# PCB.net
KiCad netlist of a schematic drawn in Altium Designer
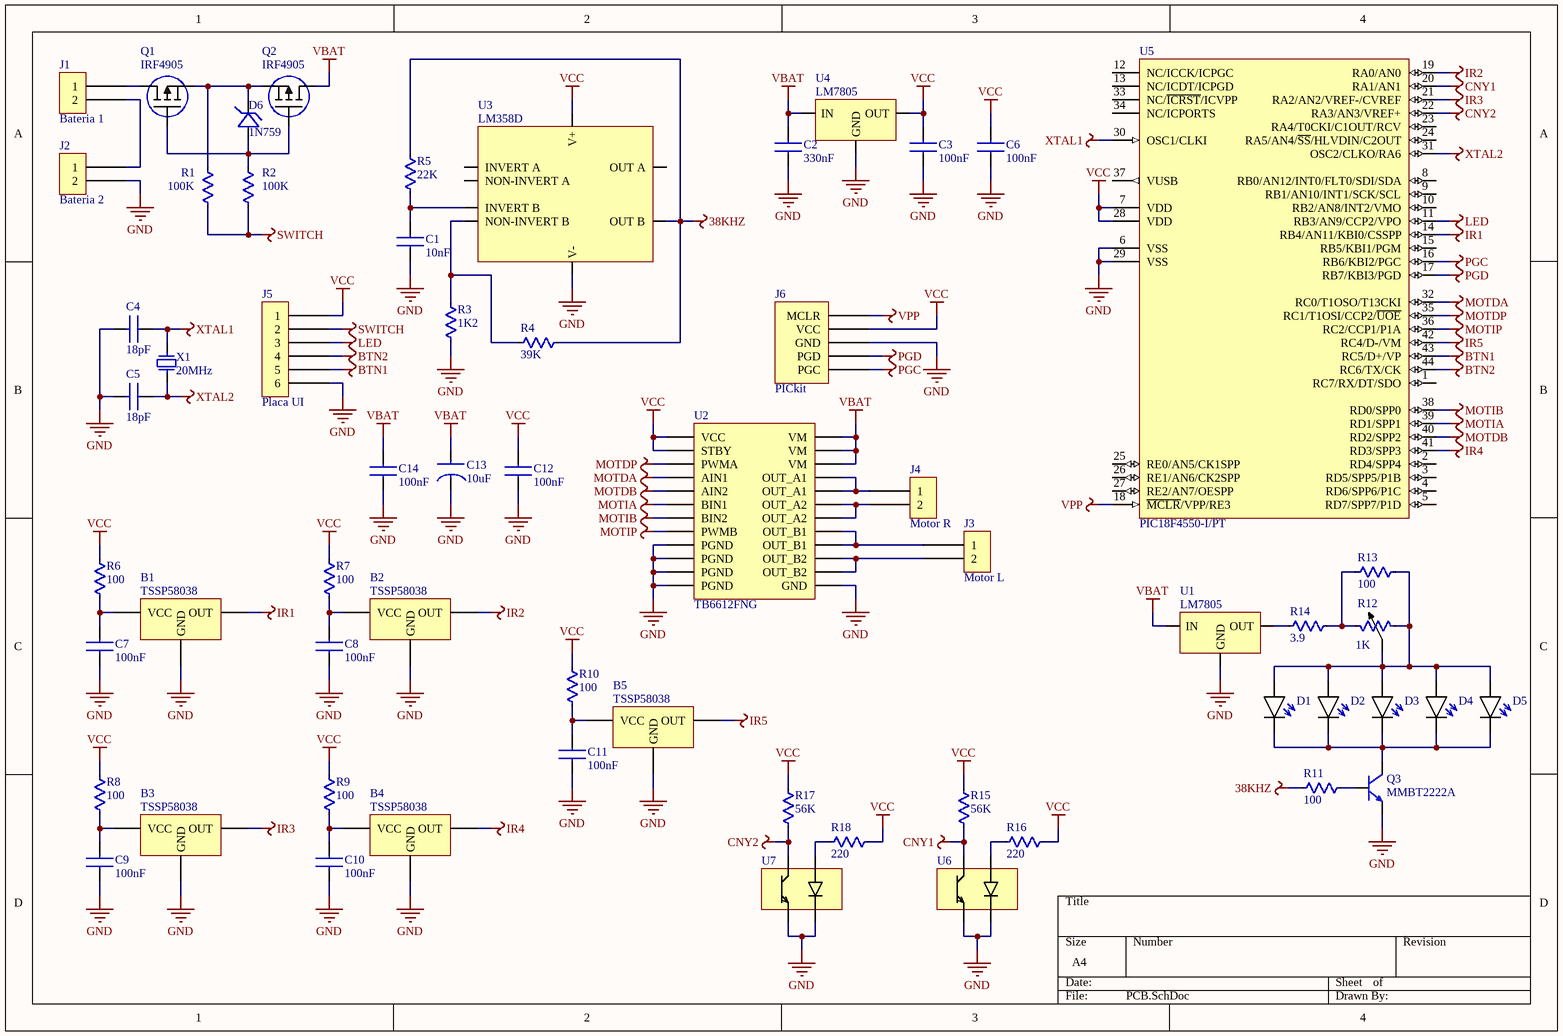
[diagram p0: PCB.SchDoc]

(export (version "E")
  (design (tool "Eeschema 10.0.6"))
  (components
    (comp (ref "B1")
      (value "TSSP58038")
      (footprint "TSSP58038")
      (libsource (lib "AltiumLibrary") (part "TSSP58038"))
    )
    (comp (ref "B2")
      (value "TSSP58038")
      (footprint "TSSP58038")
      (libsource (lib "AltiumLibrary") (part "TSSP58038"))
    )
    (comp (ref "B3")
      (value "TSSP58038")
      (footprint "TSSP58038")
      (libsource (lib "AltiumLibrary") (part "TSSP58038"))
    )
    (comp (ref "B4")
      (value "TSSP58038")
      (footprint "TSSP58038")
      (libsource (lib "AltiumLibrary") (part "TSSP58038"))
    )
    (comp (ref "B5")
      (value "TSSP58038")
      (footprint "TSSP58038")
      (libsource (lib "AltiumLibrary") (part "TSSP58038"))
    )
    (comp (ref "C1")
      (value "10nF")
      (footprint "C1206")
      (fields (field (name "Comment") "CAP-CER"))
      (libsource (lib "AltiumLibrary") (part "CAP-CER"))
    )
    (comp (ref "C2")
      (value "330nF")
      (footprint "C1206")
      (fields (field (name "Comment") "CAP-CER"))
      (libsource (lib "AltiumLibrary") (part "CAP-CER"))
    )
    (comp (ref "C3")
      (value "100nF")
      (footprint "C1206")
      (fields (field (name "Comment") "CAP-CER"))
      (libsource (lib "AltiumLibrary") (part "CAP-CER"))
    )
    (comp (ref "C4")
      (value "18pF")
      (footprint "C1206")
      (fields (field (name "Comment") "CAP-CER"))
      (libsource (lib "AltiumLibrary") (part "CAP-CER"))
    )
    (comp (ref "C5")
      (value "18pF")
      (footprint "C1206")
      (fields (field (name "Comment") "CAP-CER"))
      (libsource (lib "AltiumLibrary") (part "CAP-CER"))
    )
    (comp (ref "C6")
      (value "100nF")
      (footprint "C1206")
      (fields (field (name "Comment") "CAP-CER"))
      (libsource (lib "AltiumLibrary") (part "CAP-CER"))
    )
    (comp (ref "C7")
      (value "100nF")
      (footprint "C1206")
      (fields (field (name "Comment") "CAP-CER"))
      (libsource (lib "AltiumLibrary") (part "CAP-CER"))
    )
    (comp (ref "C8")
      (value "100nF")
      (footprint "C1206")
      (fields (field (name "Comment") "CAP-CER"))
      (libsource (lib "AltiumLibrary") (part "CAP-CER"))
    )
    (comp (ref "C9")
      (value "100nF")
      (footprint "C1206")
      (fields (field (name "Comment") "CAP-CER"))
      (libsource (lib "AltiumLibrary") (part "CAP-CER"))
    )
    (comp (ref "C10")
      (value "100nF")
      (footprint "C1206")
      (fields (field (name "Comment") "CAP-CER"))
      (libsource (lib "AltiumLibrary") (part "CAP-CER"))
    )
    (comp (ref "C11")
      (value "100nF")
      (footprint "C1206")
      (fields (field (name "Comment") "CAP-CER"))
      (libsource (lib "AltiumLibrary") (part "CAP-CER"))
    )
    (comp (ref "C12")
      (value "100nF")
      (footprint "C1206")
      (fields (field (name "Comment") "CAP-CER"))
      (libsource (lib "AltiumLibrary") (part "CAP-CER"))
    )
    (comp (ref "C13")
      (value "10uF")
      (footprint "CAP-ELEC-5x11x2mm")
      (fields (field (name "Comment") "CAP-ELEC"))
      (libsource (lib "AltiumLibrary") (part "CAP-ELEC"))
    )
    (comp (ref "C14")
      (value "100nF")
      (footprint "C1206")
      (fields (field (name "Comment") "CAP-CER"))
      (libsource (lib "AltiumLibrary") (part "CAP-CER"))
    )
    (comp (ref "D1") (value "LED") (footprint "LED-5MM-CLEAR") (libsource (lib "AltiumLibrary") (part "LED")))
    (comp (ref "D2") (value "LED") (footprint "LED-5MM-CLEAR") (libsource (lib "AltiumLibrary") (part "LED")))
    (comp (ref "D3") (value "LED") (footprint "LED-5MM-CLEAR") (libsource (lib "AltiumLibrary") (part "LED")))
    (comp (ref "D4") (value "LED") (footprint "LED-5MM-CLEAR") (libsource (lib "AltiumLibrary") (part "LED")))
    (comp (ref "D5") (value "LED") (footprint "LED-5MM-CLEAR") (libsource (lib "AltiumLibrary") (part "LED")))
    (comp (ref "D6") (value "1N759") (footprint "SOD-80") (libsource (lib "AltiumLibrary") (part "ZENER")))
    (comp (ref "J1") (value "Bateria 1") (footprint "HEADER 1x2") (libsource (lib "") (part "Header 1x2_1")))
    (comp (ref "J2") (value "Bateria 2") (footprint "HEADER 1x2") (libsource (lib "") (part "Header 1x2_1")))
    (comp (ref "J3")
      (value "Motor L")
      (footprint "HEADER 1x2")
      (libsource (lib "AltiumLibrary") (part "Header 1x2"))
    )
    (comp (ref "J4")
      (value "Motor R")
      (footprint "HEADER 1x2")
      (libsource (lib "AltiumLibrary") (part "Header 1x2"))
    )
    (comp (ref "J5")
      (value "Placa UI")
      (footprint "Header 1x6")
      (libsource (lib "AltiumLibrary") (part "Header 1x6"))
    )
    (comp (ref "J6")
      (value "PICkit")
      (footprint "Header 1x5")
      (libsource (lib "AltiumLibrary") (part "PICkit"))
    )
    (comp (ref "Q1")
      (value "IRF4905")
      (footprint "TO-220")
      (libsource (lib "AltiumLibrary") (part "P-MOSFET"))
    )
    (comp (ref "Q2")
      (value "IRF4905")
      (footprint "TO-220")
      (libsource (lib "AltiumLibrary") (part "P-MOSFET"))
    )
    (comp (ref "Q3") (value "MMBT2222A") (footprint "SOT-23") (libsource (lib "AltiumLibrary") (part "NPN")))
    (comp (ref "R1")
      (value "100K")
      (footprint "R1206")
      (fields (field (name "Comment") "RES"))
      (libsource (lib "") (part "RES_1"))
    )
    (comp (ref "R2")
      (value "100K")
      (footprint "R1206")
      (fields (field (name "Comment") "RES"))
      (libsource (lib "") (part "RES_2"))
    )
    (comp (ref "R3")
      (value "1K2")
      (footprint "R1206")
      (fields (field (name "Comment") "RES"))
      (libsource (lib "") (part "RES_2"))
    )
    (comp (ref "R4")
      (value "39K")
      (footprint "R1206")
      (fields (field (name "Comment") "RES"))
      (libsource (lib "AltiumLibrary") (part "RES"))
    )
    (comp (ref "R5")
      (value "22K")
      (footprint "R1206")
      (fields (field (name "Comment") "RES"))
      (libsource (lib "") (part "RES_2"))
    )
    (comp (ref "R6")
      (value "100")
      (footprint "R1206")
      (fields (field (name "Comment") "RES"))
      (libsource (lib "") (part "RES_2"))
    )
    (comp (ref "R7")
      (value "100")
      (footprint "R1206")
      (fields (field (name "Comment") "RES"))
      (libsource (lib "") (part "RES_2"))
    )
    (comp (ref "R8")
      (value "100")
      (footprint "R1206")
      (fields (field (name "Comment") "RES"))
      (libsource (lib "") (part "RES_2"))
    )
    (comp (ref "R9")
      (value "100")
      (footprint "R1206")
      (fields (field (name "Comment") "RES"))
      (libsource (lib "") (part "RES_2"))
    )
    (comp (ref "R10")
      (value "100")
      (footprint "R1206")
      (fields (field (name "Comment") "RES"))
      (libsource (lib "") (part "RES_2"))
    )
    (comp (ref "R11")
      (value "100")
      (footprint "R1206")
      (fields (field (name "Comment") "RES"))
      (libsource (lib "AltiumLibrary") (part "RES"))
    )
    (comp (ref "R12")
      (value "1K")
      (footprint "TRIMPOT")
      (fields (field (name "Comment") "POT"))
      (libsource (lib "AltiumLibrary") (part "POT"))
    )
    (comp (ref "R13")
      (value "100")
      (footprint "R1206")
      (fields (field (name "Comment") "RES"))
      (libsource (lib "AltiumLibrary") (part "RES"))
    )
    (comp (ref "R14")
      (value "3.9")
      (footprint "R1206")
      (fields (field (name "Comment") "RES"))
      (libsource (lib "AltiumLibrary") (part "RES"))
    )
    (comp (ref "R15")
      (value "56K")
      (footprint "R1206")
      (fields (field (name "Comment") "RES"))
      (libsource (lib "") (part "RES_2"))
    )
    (comp (ref "R16")
      (value "220")
      (footprint "R1206")
      (fields (field (name "Comment") "RES"))
      (libsource (lib "AltiumLibrary") (part "RES"))
    )
    (comp (ref "R17")
      (value "56K")
      (footprint "R1206")
      (fields (field (name "Comment") "RES"))
      (libsource (lib "") (part "RES_2"))
    )
    (comp (ref "R18")
      (value "220")
      (footprint "R1206")
      (fields (field (name "Comment") "RES"))
      (libsource (lib "AltiumLibrary") (part "RES"))
    )
    (comp (ref "U1") (value "LM7805") (footprint "TO-252") (libsource (lib "AltiumLibrary") (part "LM78XX")))
    (comp (ref "U2")
      (value "TB6612FNG")
      (footprint "SSOP24")
      (description "otor / Motion / Ignition Controllers & Drivers Brush Motor Driver IC")
      (fields (field (name "MANUFACTURER_PART_NUMBER") "TB6612FNG,C,8,EL"))
      (libsource (lib "AltiumLibrary") (part "TB6612FNG"))
    )
    (comp (ref "U3") (value "LM358D") (footprint "SOIC-8") (libsource (lib "AltiumLibrary") (part "LM358")))
    (comp (ref "U4") (value "LM7805") (footprint "TO-252") (libsource (lib "AltiumLibrary") (part "LM78XX")))
    (comp (ref "U5")
      (value "PIC18F4550-I/PT")
      (footprint "TQFP-PT44_N")
      (fields (field (name "PUBLISHER") "Altium Limited"))
      (libsource (lib "AltiumLibrary") (part "PIC18F4550-I/PT"))
    )
    (comp (ref "U6")
      (value "QRE1113GR")
      (footprint "QRE1113GR")
      (fields (field (name "MF") "ON Semiconductor"))
      (libsource (lib "AltiumLibrary") (part "QRE1113GR"))
    )
    (comp (ref "U7")
      (value "QRE1113GR")
      (footprint "QRE1113GR")
      (fields (field (name "MF") "ON Semiconductor"))
      (libsource (lib "AltiumLibrary") (part "QRE1113GR"))
    )
    (comp (ref "X1")
      (value "XTAL")
      (footprint "HC-49/S")
      (fields (field (name "FREQUENCY") "20MHz"))
      (libsource (lib "AltiumLibrary") (part "XTAL"))
    )
  )
  (nets
    (net (code "1") (name "38KHZ") (class "Default")
      (node (ref "R11") (pin "1") (pintype "passive"))
      (node (ref "R4") (pin "2") (pintype "passive"))
      (node (ref "R5") (pin "2") (pintype "passive"))
      (node (ref "U3") (pin "7") (pinfunction "OUT_B_7") (pintype "passive"))
    )
    (net (code "2") (name "BTN1") (class "Default")
      (node (ref "J5") (pin "5") (pinfunction "5_5") (pintype "passive"))
      (node (ref "U5") (pin "43") (pinfunction "RC5/D+/VP_43") (pintype "bidirectional"))
    )
    (net (code "3") (name "BTN2") (class "Default")
      (node (ref "J5") (pin "4") (pinfunction "4_4") (pintype "passive"))
      (node (ref "U5") (pin "44") (pinfunction "RC6/TX/CK_44") (pintype "bidirectional"))
    )
    (net (code "4") (name "CNY1") (class "Default")
      (node (ref "R15") (pin "1") (pintype "passive"))
      (node (ref "U5") (pin "20") (pinfunction "RA1/AN1_20") (pintype "bidirectional"))
      (node (ref "U6") (pin "C") (pinfunction "C_C") (pintype "passive"))
    )
    (net (code "5") (name "CNY2") (class "Default")
      (node (ref "R17") (pin "1") (pintype "passive"))
      (node (ref "U5") (pin "22") (pinfunction "RA3/AN3/VREF+_22") (pintype "bidirectional"))
      (node (ref "U7") (pin "C") (pinfunction "C_C") (pintype "passive"))
    )
    (net (code "6") (name "GND") (class "Default")
      (node (ref "B1") (pin "2") (pinfunction "GND_2") (pintype "passive"))
      (node (ref "B2") (pin "2") (pinfunction "GND_2") (pintype "passive"))
      (node (ref "B3") (pin "2") (pinfunction "GND_2") (pintype "passive"))
      (node (ref "B4") (pin "2") (pinfunction "GND_2") (pintype "passive"))
      (node (ref "B5") (pin "2") (pinfunction "GND_2") (pintype "passive"))
      (node (ref "C1") (pin "2") (pintype "passive"))
      (node (ref "C10") (pin "1") (pintype "passive"))
      (node (ref "C11") (pin "1") (pintype "passive"))
      (node (ref "C12") (pin "1") (pintype "passive"))
      (node (ref "C13") (pin "2") (pintype "passive"))
      (node (ref "C14") (pin "1") (pintype "passive"))
      (node (ref "C2") (pin "1") (pintype "passive"))
      (node (ref "C3") (pin "1") (pintype "passive"))
      (node (ref "C4") (pin "1") (pintype "passive"))
      (node (ref "C5") (pin "1") (pintype "passive"))
      (node (ref "C6") (pin "1") (pintype "passive"))
      (node (ref "C7") (pin "1") (pintype "passive"))
      (node (ref "C8") (pin "1") (pintype "passive"))
      (node (ref "C9") (pin "1") (pintype "passive"))
      (node (ref "J2") (pin "2") (pinfunction "2_2") (pintype "passive"))
      (node (ref "J5") (pin "6") (pinfunction "6_6") (pintype "passive"))
      (node (ref "J6") (pin "3") (pinfunction "GND_3") (pintype "power_in"))
      (node (ref "Q3") (pin "E") (pinfunction "E_E") (pintype "passive"))
      (node (ref "R3") (pin "1") (pintype "passive"))
      (node (ref "U1") (pin "2") (pinfunction "GND_2") (pintype "power_in"))
      (node (ref "U2") (pin "10") (pinfunction "PGND_10") (pintype "passive"))
      (node (ref "U2") (pin "18") (pinfunction "GND_18") (pintype "passive"))
      (node (ref "U2") (pin "3") (pinfunction "PGND_3") (pintype "passive"))
      (node (ref "U2") (pin "4") (pinfunction "PGND_4") (pintype "passive"))
      (node (ref "U2") (pin "9") (pinfunction "PGND_9") (pintype "passive"))
      (node (ref "U3") (pin "4") (pinfunction "V-_4") (pintype "passive"))
      (node (ref "U4") (pin "2") (pinfunction "GND_2") (pintype "power_in"))
      (node (ref "U5") (pin "29") (pinfunction "VSS_29") (pintype "power_in"))
      (node (ref "U5") (pin "6") (pinfunction "VSS_6") (pintype "power_in"))
      (node (ref "U6") (pin "E") (pinfunction "E_E") (pintype "passive"))
      (node (ref "U6") (pin "K") (pinfunction "K_K") (pintype "passive"))
      (node (ref "U7") (pin "E") (pinfunction "E_E") (pintype "passive"))
      (node (ref "U7") (pin "K") (pinfunction "K_K") (pintype "passive"))
    )
    (net (code "7") (name "IR1") (class "Default")
      (node (ref "B1") (pin "1") (pinfunction "OUT_1") (pintype "passive"))
      (node (ref "U5") (pin "14") (pinfunction "RB4/AN11/KBI0/CSSPP_14") (pintype "bidirectional"))
    )
    (net (code "8") (name "IR2") (class "Default")
      (node (ref "B2") (pin "1") (pinfunction "OUT_1") (pintype "passive"))
      (node (ref "U5") (pin "19") (pinfunction "RA0/AN0_19") (pintype "bidirectional"))
    )
    (net (code "9") (name "IR3") (class "Default")
      (node (ref "B3") (pin "1") (pinfunction "OUT_1") (pintype "passive"))
      (node (ref "U5") (pin "21") (pinfunction "RA2/AN2/VREF-/CVREF_21") (pintype "bidirectional"))
    )
    (net (code "10") (name "IR4") (class "Default")
      (node (ref "B4") (pin "1") (pinfunction "OUT_1") (pintype "passive"))
      (node (ref "U5") (pin "41") (pinfunction "RD3/SPP3_41") (pintype "bidirectional"))
    )
    (net (code "11") (name "IR5") (class "Default")
      (node (ref "B5") (pin "1") (pinfunction "OUT_1") (pintype "passive"))
      (node (ref "U5") (pin "42") (pinfunction "RC4/D-/VM_42") (pintype "bidirectional"))
    )
    (net (code "12") (name "LED") (class "Default")
      (node (ref "J5") (pin "3") (pinfunction "3_3") (pintype "passive"))
      (node (ref "U5") (pin "11") (pinfunction "RB3/AN9/CCP2/VPO_11") (pintype "bidirectional"))
    )
    (net (code "13") (name "MOTDA") (class "Default")
      (node (ref "U2") (pin "21") (pinfunction "AIN1_21") (pintype "passive"))
      (node (ref "U5") (pin "32") (pinfunction "RC0/T1OSO/T13CKI_32") (pintype "bidirectional"))
    )
    (net (code "14") (name "MOTDB") (class "Default")
      (node (ref "U2") (pin "22") (pinfunction "AIN2_22") (pintype "passive"))
      (node (ref "U5") (pin "40") (pinfunction "RD2/SPP2_40") (pintype "bidirectional"))
    )
    (net (code "15") (name "MOTDP") (class "Default")
      (node (ref "U2") (pin "23") (pinfunction "PWMA_23") (pintype "passive"))
      (node (ref "U5") (pin "35") (pinfunction "RC1/T1OSI/CCP2/~{UOE}_35") (pintype "bidirectional"))
    )
    (net (code "16") (name "MOTIA") (class "Default")
      (node (ref "U2") (pin "17") (pinfunction "BIN1_17") (pintype "passive"))
      (node (ref "U5") (pin "39") (pinfunction "RD1/SPP1_39") (pintype "bidirectional"))
    )
    (net (code "17") (name "MOTIB") (class "Default")
      (node (ref "U2") (pin "16") (pinfunction "BIN2_16") (pintype "passive"))
      (node (ref "U5") (pin "38") (pinfunction "RD0/SPP0_38") (pintype "bidirectional"))
    )
    (net (code "18") (name "MOTIP") (class "Default")
      (node (ref "U2") (pin "15") (pinfunction "PWMB_15") (pintype "passive"))
      (node (ref "U5") (pin "36") (pinfunction "RC2/CCP1/P1A_36") (pintype "bidirectional"))
    )
    (net (code "19") (name "Net-(B1-VCC)") (class "Default")
      (node (ref "B1") (pin "3") (pinfunction "VCC_3") (pintype "passive"))
      (node (ref "C7") (pin "2") (pintype "passive"))
      (node (ref "R6") (pin "1") (pintype "passive"))
    )
    (net (code "20") (name "Net-(B2-VCC)") (class "Default")
      (node (ref "B2") (pin "3") (pinfunction "VCC_3") (pintype "passive"))
      (node (ref "C8") (pin "2") (pintype "passive"))
      (node (ref "R7") (pin "1") (pintype "passive"))
    )
    (net (code "21") (name "Net-(B3-VCC)") (class "Default")
      (node (ref "B3") (pin "3") (pinfunction "VCC_3") (pintype "passive"))
      (node (ref "C9") (pin "2") (pintype "passive"))
      (node (ref "R8") (pin "1") (pintype "passive"))
    )
    (net (code "22") (name "Net-(B4-VCC)") (class "Default")
      (node (ref "B4") (pin "3") (pinfunction "VCC_3") (pintype "passive"))
      (node (ref "C10") (pin "2") (pintype "passive"))
      (node (ref "R9") (pin "1") (pintype "passive"))
    )
    (net (code "23") (name "Net-(B5-VCC)") (class "Default")
      (node (ref "B5") (pin "3") (pinfunction "VCC_3") (pintype "passive"))
      (node (ref "C11") (pin "2") (pintype "passive"))
      (node (ref "R10") (pin "1") (pintype "passive"))
    )
    (net (code "24") (name "Net-(D1-PadA)") (class "Default")
      (node (ref "D1") (pin "A") (pintype "passive"))
      (node (ref "D2") (pin "A") (pintype "passive"))
      (node (ref "D3") (pin "A") (pintype "passive"))
      (node (ref "D4") (pin "A") (pintype "passive"))
      (node (ref "D5") (pin "A") (pintype "passive"))
      (node (ref "R12") (pin "2") (pintype "passive"))
      (node (ref "R12") (pin "3") (pintype "passive"))
      (node (ref "R13") (pin "2") (pintype "passive"))
    )
    (net (code "25") (name "Net-(D1-PadK)") (class "Default")
      (node (ref "D1") (pin "K") (pintype "passive"))
      (node (ref "D2") (pin "K") (pintype "passive"))
      (node (ref "D3") (pin "K") (pintype "passive"))
      (node (ref "D4") (pin "K") (pintype "passive"))
      (node (ref "D5") (pin "K") (pintype "passive"))
      (node (ref "Q3") (pin "C") (pinfunction "C_C") (pintype "passive"))
    )
    (net (code "26") (name "Net-(D6-PadA)") (class "Default")
      (node (ref "D6") (pin "A") (pintype "passive"))
      (node (ref "Q1") (pin "G") (pintype "passive"))
      (node (ref "Q2") (pin "G") (pintype "passive"))
      (node (ref "R2") (pin "2") (pintype "passive"))
    )
    (net (code "27") (name "Net-(D6-PadK)") (class "Default")
      (node (ref "D6") (pin "K") (pintype "passive"))
      (node (ref "Q1") (pin "S") (pintype "passive"))
      (node (ref "Q2") (pin "S") (pintype "passive"))
      (node (ref "R1") (pin "1") (pintype "passive"))
    )
    (net (code "28") (name "Net-(J1-Pad1)") (class "Default")
      (node (ref "J1") (pin "1") (pinfunction "1_1") (pintype "passive"))
      (node (ref "Q1") (pin "D") (pintype "passive"))
    )
    (net (code "29") (name "Net-(J1-Pad2)") (class "Default")
      (node (ref "J1") (pin "2") (pinfunction "2_2") (pintype "passive"))
      (node (ref "J2") (pin "1") (pinfunction "1_1") (pintype "passive"))
    )
    (net (code "30") (name "Net-(J3-Pad1)") (class "Default")
      (node (ref "J3") (pin "1") (pinfunction "1_1") (pintype "passive"))
      (node (ref "U2") (pin "11") (pinfunction "OUT_B1_11") (pintype "passive"))
      (node (ref "U2") (pin "12") (pinfunction "OUT_B1_12") (pintype "passive"))
    )
    (net (code "31") (name "Net-(J3-Pad2)") (class "Default")
      (node (ref "J3") (pin "2") (pinfunction "2_2") (pintype "passive"))
      (node (ref "U2") (pin "7") (pinfunction "OUT_B2_7") (pintype "passive"))
      (node (ref "U2") (pin "8") (pinfunction "OUT_B2_8") (pintype "passive"))
    )
    (net (code "32") (name "Net-(J4-Pad1)") (class "Default")
      (node (ref "J4") (pin "1") (pinfunction "1_1") (pintype "passive"))
      (node (ref "U2") (pin "1") (pinfunction "OUT_A1_1") (pintype "passive"))
      (node (ref "U2") (pin "2") (pinfunction "OUT_A1_2") (pintype "passive"))
    )
    (net (code "33") (name "Net-(J4-Pad2)") (class "Default")
      (node (ref "J4") (pin "2") (pinfunction "2_2") (pintype "passive"))
      (node (ref "U2") (pin "5") (pinfunction "OUT_A2_5") (pintype "passive"))
      (node (ref "U2") (pin "6") (pinfunction "OUT_A2_6") (pintype "passive"))
    )
    (net (code "34") (name "Net-(Q3-PadB)") (class "Default")
      (node (ref "Q3") (pin "B") (pinfunction "B_B") (pintype "passive"))
      (node (ref "R11") (pin "2") (pintype "passive"))
    )
    (net (code "35") (name "Net-(R12-Pad1)") (class "Default")
      (node (ref "R12") (pin "1") (pintype "passive"))
      (node (ref "R13") (pin "1") (pintype "passive"))
      (node (ref "R14") (pin "2") (pintype "passive"))
    )
    (net (code "36") (name "Net-(R16-Pad1)") (class "Default")
      (node (ref "R16") (pin "1") (pintype "passive"))
      (node (ref "U6") (pin "A") (pinfunction "A_A") (pintype "passive"))
    )
    (net (code "37") (name "Net-(R18-Pad1)") (class "Default")
      (node (ref "R18") (pin "1") (pintype "passive"))
      (node (ref "U7") (pin "A") (pinfunction "A_A") (pintype "passive"))
    )
    (net (code "38") (name "Net-(U1-OUT)") (class "Default")
      (node (ref "R14") (pin "1") (pintype "passive"))
      (node (ref "U1") (pin "3") (pinfunction "OUT_3") (pintype "power_in"))
    )
    (net (code "39") (name "Net-(U3-INVERT_B)") (class "Default")
      (node (ref "C1") (pin "1") (pintype "passive"))
      (node (ref "R5") (pin "1") (pintype "passive"))
      (node (ref "U3") (pin "6") (pinfunction "INVERT_B_6") (pintype "passive"))
    )
    (net (code "40") (name "Net-(U3-NON-INVERT_B)") (class "Default")
      (node (ref "R3") (pin "2") (pintype "passive"))
      (node (ref "R4") (pin "1") (pintype "passive"))
      (node (ref "U3") (pin "5") (pinfunction "NON-INVERT_B_5") (pintype "passive"))
    )
    (net (code "41") (name "PGC") (class "Default")
      (node (ref "J6") (pin "5") (pinfunction "PGC_5") (pintype "passive"))
      (node (ref "U5") (pin "16") (pinfunction "RB6/KBI2/PGC_16") (pintype "bidirectional"))
    )
    (net (code "42") (name "PGD") (class "Default")
      (node (ref "J6") (pin "4") (pinfunction "PGD_4") (pintype "passive"))
      (node (ref "U5") (pin "17") (pinfunction "RB7/KBI3/PGD_17") (pintype "bidirectional"))
    )
    (net (code "43") (name "SWITCH") (class "Default")
      (node (ref "J5") (pin "2") (pinfunction "2_2") (pintype "passive"))
      (node (ref "R1") (pin "2") (pintype "passive"))
      (node (ref "R2") (pin "1") (pintype "passive"))
    )
    (net (code "44") (name "VBAT") (class "Default")
      (node (ref "C13") (pin "1") (pintype "passive"))
      (node (ref "C14") (pin "2") (pintype "passive"))
      (node (ref "C2") (pin "2") (pintype "passive"))
      (node (ref "Q2") (pin "D") (pintype "passive"))
      (node (ref "U1") (pin "1") (pinfunction "IN_1") (pintype "power_in"))
      (node (ref "U2") (pin "13") (pinfunction "VM_13") (pintype "passive"))
      (node (ref "U2") (pin "14") (pinfunction "VM_14") (pintype "passive"))
      (node (ref "U2") (pin "24") (pinfunction "VM_24") (pintype "passive"))
      (node (ref "U4") (pin "1") (pinfunction "IN_1") (pintype "power_in"))
    )
    (net (code "45") (name "VCC") (class "Default")
      (node (ref "C12") (pin "2") (pintype "passive"))
      (node (ref "C3") (pin "2") (pintype "passive"))
      (node (ref "C6") (pin "2") (pintype "passive"))
      (node (ref "J5") (pin "1") (pinfunction "1_1") (pintype "passive"))
      (node (ref "J6") (pin "2") (pinfunction "VCC_2") (pintype "power_in"))
      (node (ref "R10") (pin "2") (pintype "passive"))
      (node (ref "R15") (pin "2") (pintype "passive"))
      (node (ref "R16") (pin "2") (pintype "passive"))
      (node (ref "R17") (pin "2") (pintype "passive"))
      (node (ref "R18") (pin "2") (pintype "passive"))
      (node (ref "R6") (pin "2") (pintype "passive"))
      (node (ref "R7") (pin "2") (pintype "passive"))
      (node (ref "R8") (pin "2") (pintype "passive"))
      (node (ref "R9") (pin "2") (pintype "passive"))
      (node (ref "U2") (pin "19") (pinfunction "STBY_19") (pintype "passive"))
      (node (ref "U2") (pin "20") (pinfunction "VCC_20") (pintype "power_in"))
      (node (ref "U3") (pin "8") (pinfunction "V+_8") (pintype "passive"))
      (node (ref "U4") (pin "3") (pinfunction "OUT_3") (pintype "power_in"))
      (node (ref "U5") (pin "28") (pinfunction "VDD_28") (pintype "power_in"))
      (node (ref "U5") (pin "7") (pinfunction "VDD_7") (pintype "power_in"))
    )
    (net (code "46") (name "VPP") (class "Default")
      (node (ref "J6") (pin "1") (pinfunction "MCLR_1") (pintype "passive"))
      (node (ref "U5") (pin "18") (pinfunction "~{MCLR}/VPP/RE3_18") (pintype "input"))
    )
    (net (code "47") (name "XTAL1") (class "Default")
      (node (ref "C4") (pin "2") (pintype "passive"))
      (node (ref "U5") (pin "30") (pinfunction "OSC1/CLKI_30") (pintype "input"))
      (node (ref "X1") (pin "2") (pintype "passive"))
    )
    (net (code "48") (name "XTAL2") (class "Default")
      (node (ref "C5") (pin "2") (pintype "passive"))
      (node (ref "U5") (pin "31") (pinfunction "OSC2/CLKO/RA6_31") (pintype "bidirectional"))
      (node (ref "X1") (pin "1") (pintype "passive"))
    )
    (net (code "49") (name "unconnected-(U3-INVERT_A-Pad2)") (class "Default")
      (node (ref "U3") (pin "2") (pinfunction "INVERT_A_2") (pintype "passive"))
    )
    (net (code "50") (name "unconnected-(U3-NON-INVERT_A-Pad3)") (class "Default")
      (node (ref "U3") (pin "3") (pinfunction "NON-INVERT_A_3") (pintype "passive"))
    )
    (net (code "51") (name "unconnected-(U3-OUT_A-Pad1)") (class "Default")
      (node (ref "U3") (pin "1") (pinfunction "OUT_A_1") (pintype "passive"))
    )
    (net (code "52") (name "unconnected-(U5-NC{slash}ICCK{slash}ICPGC-Pad12)") (class "Default")
      (node (ref "U5") (pin "12") (pinfunction "NC/ICCK/ICPGC_12") (pintype "passive"))
    )
    (net (code "53") (name "unconnected-(U5-NC{slash}ICDT{slash}ICPGD-Pad13)") (class "Default")
      (node (ref "U5") (pin "13") (pinfunction "NC/ICDT/ICPGD_13") (pintype "passive"))
    )
    (net (code "54") (name "unconnected-(U5-NC{slash}ICPORTS-Pad34)") (class "Default")
      (node (ref "U5") (pin "34") (pinfunction "NC/ICPORTS_34") (pintype "passive"))
    )
    (net (code "55") (name "unconnected-(U5-NC{slash}~{ICRST}{slash}ICVPP-Pad33)") (class "Default")
      (node (ref "U5") (pin "33") (pinfunction "NC/~{ICRST}/ICVPP_33") (pintype "passive"))
    )
    (net (code "56") (name "unconnected-(U5-RA4{slash}T0CKI{slash}C1OUT{slash}RCV-Pad23)") (class "Default")
      (node (ref "U5") (pin "23") (pinfunction "RA4/T0CKI/C1OUT/RCV_23") (pintype "bidirectional"))
    )
    (net (code "57") (name "unconnected-(U5-RA5{slash}AN4{slash}~{SS}{slash}HLVDIN{slash}C2OUT-Pad24)") (class "Default")
      (node (ref "U5") (pin "24") (pinfunction "RA5/AN4/~{SS}/HLVDIN/C2OUT_24") (pintype "bidirectional"))
    )
    (net (code "58") (name "unconnected-(U5-RB0{slash}AN12{slash}INT0{slash}FLT0{slash}SDI{slash}SDA-Pad8)") (class "Default")
      (node (ref "U5") (pin "8") (pinfunction "RB0/AN12/INT0/FLT0/SDI/SDA_8") (pintype "bidirectional"))
    )
    (net (code "59") (name "unconnected-(U5-RB1{slash}AN10{slash}INT1{slash}SCK{slash}SCL-Pad9)") (class "Default")
      (node (ref "U5") (pin "9") (pinfunction "RB1/AN10/INT1/SCK/SCL_9") (pintype "bidirectional"))
    )
    (net (code "60") (name "unconnected-(U5-RB2{slash}AN8{slash}INT2{slash}VMO-Pad10)") (class "Default")
      (node (ref "U5") (pin "10") (pinfunction "RB2/AN8/INT2/VMO_10") (pintype "bidirectional"))
    )
    (net (code "61") (name "unconnected-(U5-RB5{slash}KBI1{slash}PGM-Pad15)") (class "Default")
      (node (ref "U5") (pin "15") (pinfunction "RB5/KBI1/PGM_15") (pintype "bidirectional"))
    )
    (net (code "62") (name "unconnected-(U5-RC7{slash}RX{slash}DT{slash}SDO-Pad1)") (class "Default")
      (node (ref "U5") (pin "1") (pinfunction "RC7/RX/DT/SDO_1") (pintype "bidirectional"))
    )
    (net (code "63") (name "unconnected-(U5-RD4{slash}SPP4-Pad2)") (class "Default")
      (node (ref "U5") (pin "2") (pinfunction "RD4/SPP4_2") (pintype "bidirectional"))
    )
    (net (code "64") (name "unconnected-(U5-RD5{slash}SPP5{slash}P1B-Pad3)") (class "Default")
      (node (ref "U5") (pin "3") (pinfunction "RD5/SPP5/P1B_3") (pintype "bidirectional"))
    )
    (net (code "65") (name "unconnected-(U5-RD6{slash}SPP6{slash}P1C-Pad4)") (class "Default")
      (node (ref "U5") (pin "4") (pinfunction "RD6/SPP6/P1C_4") (pintype "bidirectional"))
    )
    (net (code "66") (name "unconnected-(U5-RD7{slash}SPP7{slash}P1D-Pad5)") (class "Default")
      (node (ref "U5") (pin "5") (pinfunction "RD7/SPP7/P1D_5") (pintype "bidirectional"))
    )
    (net (code "67") (name "unconnected-(U5-RE0{slash}AN5{slash}CK1SPP-Pad25)") (class "Default")
      (node (ref "U5") (pin "25") (pinfunction "RE0/AN5/CK1SPP_25") (pintype "bidirectional"))
    )
    (net (code "68") (name "unconnected-(U5-RE1{slash}AN6{slash}CK2SPP-Pad26)") (class "Default")
      (node (ref "U5") (pin "26") (pinfunction "RE1/AN6/CK2SPP_26") (pintype "bidirectional"))
    )
    (net (code "69") (name "unconnected-(U5-RE2{slash}AN7{slash}OESPP-Pad27)") (class "Default")
      (node (ref "U5") (pin "27") (pinfunction "RE2/AN7/OESPP_27") (pintype "bidirectional"))
    )
    (net (code "70") (name "unconnected-(U5-VUSB-Pad37)") (class "Default")
      (node (ref "U5") (pin "37") (pinfunction "VUSB_37") (pintype "output"))
    )
  )
)
